# OV5640_Camera.net
KiCad netlist of a schematic drawn in Altium Designer
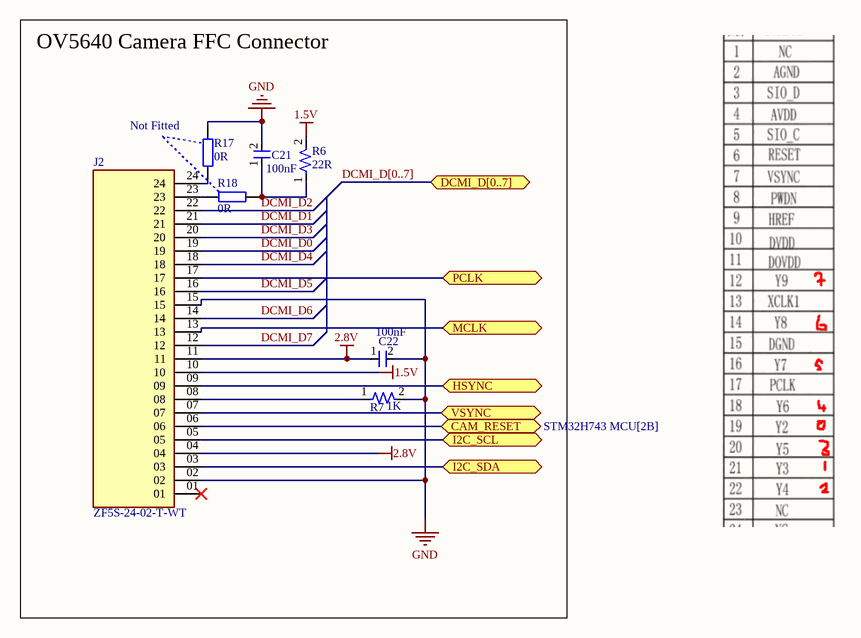
[diagram p0: OV5640 Camera.SchDoc]

(export (version "E")
  (design (tool "Eeschema 10.0.6"))
  (components
    (comp (ref "C21")
      (value "0603")
      (footprint "0603 Cap")
      (fields (field (name "C") "100nF"))
      (libsource (lib "VoltaRoket") (part "0603 Cap"))
    )
    (comp (ref "C22")
      (value "0603")
      (footprint "0603 Cap")
      (fields (field (name "C") "100nF"))
      (libsource (lib "VoltaRoket") (part "0603 Cap"))
    )
    (comp (ref "J2")
      (value "ZF5S-24-02-T-WT")
      (footprint "SAMTEC_ZF5S-24-02-T-WT")
      (libsource (lib "ZF5S-24-02-T-WT") (part "ZF5S-24-02-T-WT"))
    )
    (comp (ref "R6")
      (value "0603")
      (footprint "0603 Res")
      (fields (field (name "R") "22R"))
      (libsource (lib "VoltaRoket") (part "0603 Res"))
    )
    (comp (ref "R7")
      (value "0603")
      (footprint "0603 Res")
      (fields (field (name "R") "1K"))
      (libsource (lib "VoltaRoket") (part "0603 Res"))
    )
    (comp (ref "R17")
      (value "0R")
      (footprint "RES_0402")
      (description "Resistor SMD 0402")
      (libsource (lib "Phills_Lib") (part "RES_0402"))
    )
    (comp (ref "R18")
      (value "0R")
      (footprint "RES_0402")
      (description "Resistor SMD 0402")
      (libsource (lib "Phills_Lib") (part "RES_0402"))
    )
  )
  (nets
    (net (code "1") (name "/CAM_RESET") (class "Default")
      (node (ref "J2") (pin "06") (pinfunction "06_06") (pintype "passive"))
    )
    (net (code "2") (name "/DCMI_D0") (class "Default")
      (node (ref "J2") (pin "19") (pinfunction "19_19") (pintype "passive"))
    )
    (net (code "3") (name "/DCMI_D1") (class "Default")
      (node (ref "J2") (pin "21") (pinfunction "21_21") (pintype "passive"))
    )
    (net (code "4") (name "/DCMI_D2") (class "Default")
      (node (ref "J2") (pin "22") (pinfunction "22_22") (pintype "passive"))
    )
    (net (code "5") (name "/DCMI_D3") (class "Default")
      (node (ref "J2") (pin "20") (pinfunction "20_20") (pintype "passive"))
    )
    (net (code "6") (name "/DCMI_D4") (class "Default")
      (node (ref "J2") (pin "18") (pinfunction "18_18") (pintype "passive"))
    )
    (net (code "7") (name "/DCMI_D5") (class "Default")
      (node (ref "J2") (pin "16") (pinfunction "16_16") (pintype "passive"))
    )
    (net (code "8") (name "/DCMI_D6") (class "Default")
      (node (ref "J2") (pin "14") (pinfunction "14_14") (pintype "passive"))
    )
    (net (code "9") (name "/DCMI_D7") (class "Default")
      (node (ref "J2") (pin "12") (pinfunction "12_12") (pintype "passive"))
    )
    (net (code "11") (name "/HSYNC") (class "Default")
      (node (ref "J2") (pin "09") (pinfunction "09_09") (pintype "passive"))
    )
    (net (code "12") (name "/I2C_SCL") (class "Default")
      (node (ref "J2") (pin "05") (pinfunction "05_05") (pintype "passive"))
    )
    (net (code "13") (name "/I2C_SDA") (class "Default")
      (node (ref "J2") (pin "03") (pinfunction "03_03") (pintype "passive"))
    )
    (net (code "14") (name "/MCLK") (class "Default")
      (node (ref "J2") (pin "13") (pinfunction "13_13") (pintype "passive"))
    )
    (net (code "15") (name "/PCLK") (class "Default")
      (node (ref "J2") (pin "17") (pinfunction "17_17") (pintype "passive"))
    )
    (net (code "16") (name "/VSYNC") (class "Default")
      (node (ref "J2") (pin "07") (pinfunction "07_07") (pintype "passive"))
    )
    (net (code "17") (name "1.5V") (class "Default")
      (node (ref "J2") (pin "10") (pinfunction "10_10") (pintype "passive"))
      (node (ref "R6") (pin "2") (pinfunction "2_2") (pintype "passive"))
    )
    (net (code "18") (name "2.8V") (class "Default")
      (node (ref "C22") (pin "1") (pinfunction "1_1") (pintype "passive"))
      (node (ref "J2") (pin "04") (pinfunction "04_04") (pintype "passive"))
      (node (ref "J2") (pin "11") (pinfunction "11_11") (pintype "passive"))
    )
    (net (code "19") (name "GND") (class "Default")
      (node (ref "C21") (pin "2") (pinfunction "2_2") (pintype "passive"))
      (node (ref "C22") (pin "2") (pinfunction "2_2") (pintype "passive"))
      (node (ref "J2") (pin "02") (pinfunction "02_02") (pintype "passive"))
      (node (ref "J2") (pin "15") (pinfunction "15_15") (pintype "passive"))
      (node (ref "R17") (pin "2") (pinfunction "2_2") (pintype "passive"))
      (node (ref "R7") (pin "2") (pinfunction "2_2") (pintype "passive"))
    )
    (net (code "20") (name "Net-(C21-Pad1)") (class "Default")
      (node (ref "C21") (pin "1") (pinfunction "1_1") (pintype "passive"))
      (node (ref "R18") (pin "1") (pinfunction "1_1") (pintype "passive"))
      (node (ref "R6") (pin "1") (pinfunction "1_1") (pintype "passive"))
    )
    (net (code "21") (name "Net-(J2-Pad08)") (class "Default")
      (node (ref "J2") (pin "08") (pinfunction "08_08") (pintype "passive"))
      (node (ref "R7") (pin "1") (pinfunction "1_1") (pintype "passive"))
    )
    (net (code "22") (name "Net-(J2-Pad23)") (class "Default")
      (node (ref "J2") (pin "23") (pinfunction "23_23") (pintype "passive"))
      (node (ref "R18") (pin "2") (pinfunction "2_2") (pintype "passive"))
    )
    (net (code "23") (name "Net-(J2-Pad24)") (class "Default")
      (node (ref "J2") (pin "24") (pinfunction "24_24") (pintype "passive"))
      (node (ref "R17") (pin "1") (pinfunction "1_1") (pintype "passive"))
    )
    (net (code "24") (name "unconnected-(J2-Pad01)") (class "Default")
      (node (ref "J2") (pin "01") (pinfunction "01_01") (pintype "passive+no_connect"))
    )
  )
)
